# 171-5782_Redux.net
KiCad netlist of a schematic drawn in Altium Designer
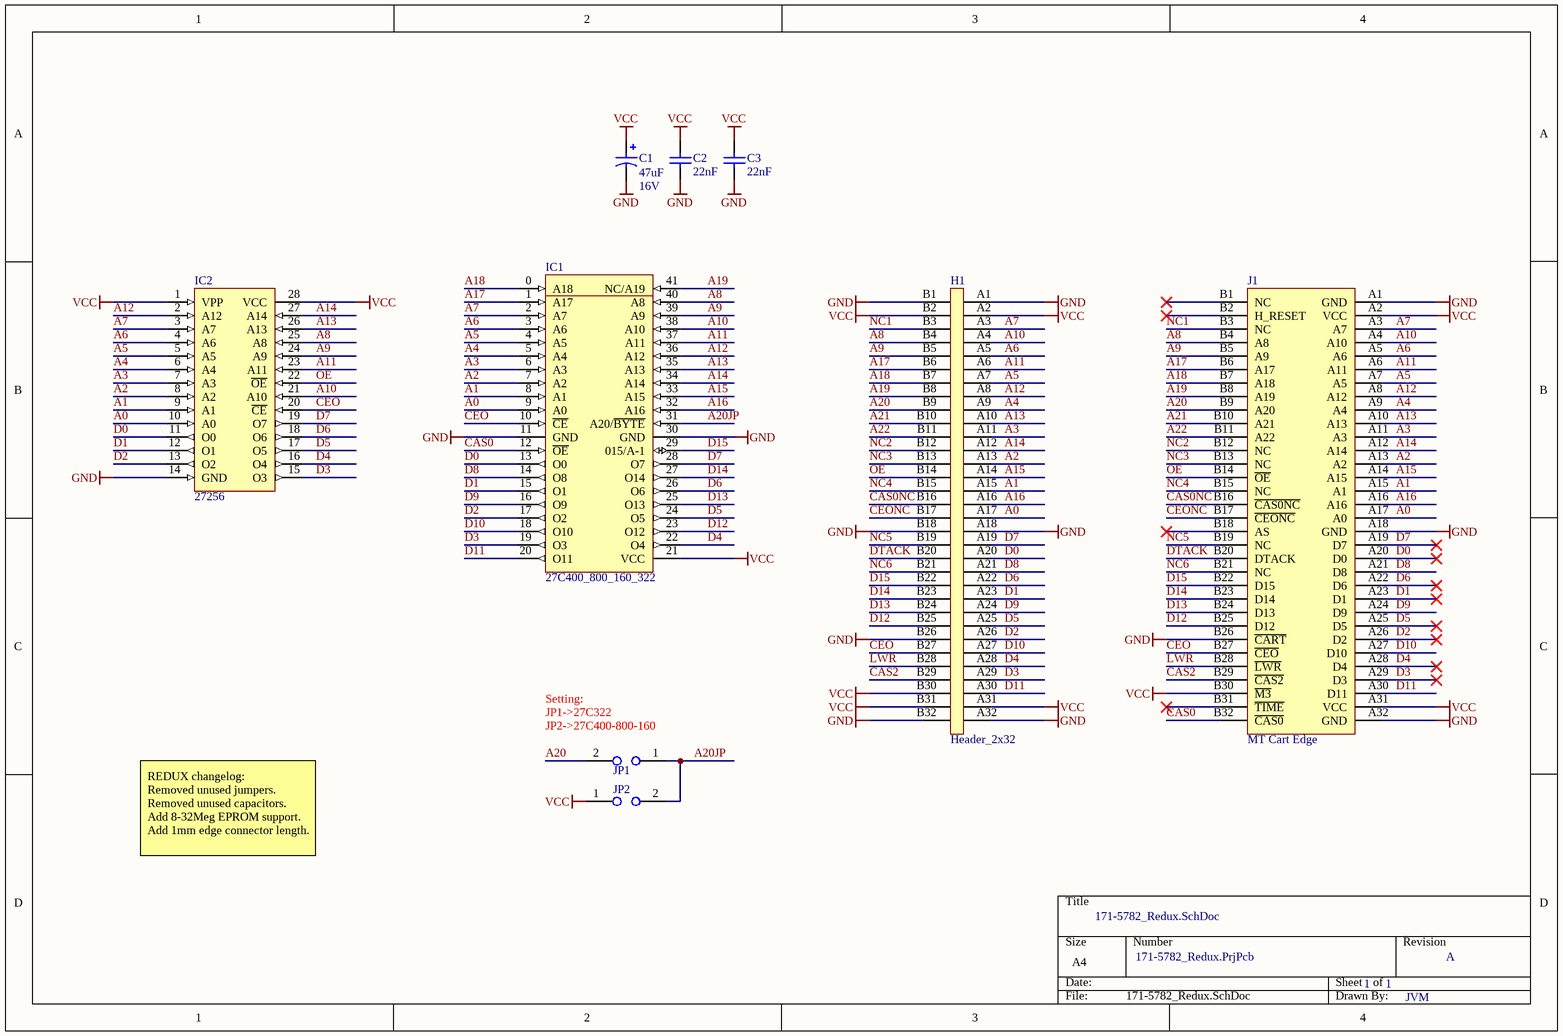
[diagram p0: 171-5782_Redux.SchDoc]

(export (version "E")
  (design (tool "Eeschema 10.0.6"))
  (components
    (comp (ref "C1")
      (value "47uF")
      (footprint "CapPol Mirror")
      (description "Polarized Capacitor, 2.54mm Pitch, 5mm Width, mirrored")
      (fields (field (name "VOLTAGE") "16V") (field (name "Comment") "Cap2.54P5.0D"))
      (libsource (lib "171-5782") (part "Cap2.54P5.0D_mirror"))
    )
    (comp (ref "C2")
      (value "22nF")
      (footprint "CapCer")
      (description "Capacitor (THT), Ceramic, 5.08mm Pitch")
      (fields (field (name "Comment") "CapCer"))
      (libsource (lib "171-5782") (part "CapCer"))
    )
    (comp (ref "C3")
      (value "22nF")
      (footprint "CapCer")
      (description "Capacitor (THT), Ceramic, 5.08mm Pitch")
      (fields (field (name "Comment") "CapCer"))
      (libsource (lib "171-5782") (part "CapCer"))
    )
    (comp (ref "H1")
      (value "Header_2x32")
      (footprint "Header_2x32")
      (libsource (lib "171-5782") (part "Header_2x32"))
    )
    (comp (ref "IC1")
      (value "27C400_800_160_322")
      (footprint "27C400_800_160_322")
      (description "27C400_800_160_322 EPROM combined footprint")
      (libsource (lib "171-5782") (part "27C400_800_160_322"))
    )
    (comp (ref "IC2")
      (value "27256")
      (footprint "27256")
      (description "256K EPROM")
      (libsource (lib "171-5782") (part "27256"))
    )
    (comp (ref "J1")
      (value "MT Cart Edge")
      (footprint "MT_Cart_Edge")
      (libsource (lib "171-5782") (part "MT_CART_EDGE_CON"))
    )
    (comp (ref "JP1")
      (value "SolderBridge")
      (footprint "SOLDER_BRIDGE")
      (description "Solder Bridge")
      (libsource (lib "171-5782") (part "SolderBridge"))
    )
    (comp (ref "JP2")
      (value "SolderBridge")
      (footprint "SOLDER_BRIDGE")
      (description "Solder Bridge")
      (libsource (lib "171-5782") (part "SolderBridge"))
    )
  )
  (nets
    (net (code "1") (name "/A0") (class "Default")
      (node (ref "H1") (pin "A17") (pintype "passive"))
      (node (ref "IC1") (pin "9") (pinfunction "A0_9") (pintype "input"))
      (node (ref "IC2") (pin "10") (pinfunction "A0_10") (pintype "input"))
      (node (ref "J1") (pin "A17") (pinfunction "A0_A17") (pintype "passive"))
    )
    (net (code "2") (name "/A1") (class "Default")
      (node (ref "H1") (pin "A15") (pintype "passive"))
      (node (ref "IC1") (pin "8") (pinfunction "A1_8") (pintype "input"))
      (node (ref "IC2") (pin "9") (pinfunction "A1_9") (pintype "input"))
      (node (ref "J1") (pin "A15") (pinfunction "A1_A15") (pintype "passive"))
    )
    (net (code "3") (name "/A2") (class "Default")
      (node (ref "H1") (pin "A13") (pintype "passive"))
      (node (ref "IC1") (pin "7") (pinfunction "A2_7") (pintype "input"))
      (node (ref "IC2") (pin "8") (pinfunction "A2_8") (pintype "input"))
      (node (ref "J1") (pin "A13") (pinfunction "A2_A13") (pintype "passive"))
    )
    (net (code "4") (name "/A3") (class "Default")
      (node (ref "H1") (pin "A11") (pintype "passive"))
      (node (ref "IC1") (pin "6") (pinfunction "A3_6") (pintype "input"))
      (node (ref "IC2") (pin "7") (pinfunction "A3_7") (pintype "input"))
      (node (ref "J1") (pin "A11") (pinfunction "A3_A11") (pintype "passive"))
    )
    (net (code "5") (name "/A4") (class "Default")
      (node (ref "H1") (pin "A9") (pintype "passive"))
      (node (ref "IC1") (pin "5") (pinfunction "A4_5") (pintype "input"))
      (node (ref "IC2") (pin "6") (pinfunction "A4_6") (pintype "input"))
      (node (ref "J1") (pin "A9") (pinfunction "A4_A9") (pintype "passive"))
    )
    (net (code "6") (name "/A5") (class "Default")
      (node (ref "H1") (pin "A7") (pintype "passive"))
      (node (ref "IC1") (pin "4") (pinfunction "A5_4") (pintype "input"))
      (node (ref "IC2") (pin "5") (pinfunction "A5_5") (pintype "input"))
      (node (ref "J1") (pin "A7") (pinfunction "A5_A7") (pintype "passive"))
    )
    (net (code "7") (name "/A6") (class "Default")
      (node (ref "H1") (pin "A5") (pintype "passive"))
      (node (ref "IC1") (pin "3") (pinfunction "A6_3") (pintype "input"))
      (node (ref "IC2") (pin "4") (pinfunction "A6_4") (pintype "input"))
      (node (ref "J1") (pin "A5") (pinfunction "A6_A5") (pintype "passive"))
    )
    (net (code "8") (name "/A7") (class "Default")
      (node (ref "H1") (pin "A3") (pintype "passive"))
      (node (ref "IC1") (pin "2") (pinfunction "A7_2") (pintype "input"))
      (node (ref "IC2") (pin "3") (pinfunction "A7_3") (pintype "input"))
      (node (ref "J1") (pin "A3") (pinfunction "A7_A3") (pintype "passive"))
    )
    (net (code "9") (name "/A8") (class "Default")
      (node (ref "H1") (pin "B4") (pintype "passive"))
      (node (ref "IC1") (pin "40") (pinfunction "A8_40") (pintype "input"))
      (node (ref "IC2") (pin "25") (pinfunction "A8_25") (pintype "input"))
      (node (ref "J1") (pin "B4") (pinfunction "A8_B4") (pintype "passive"))
    )
    (net (code "10") (name "/A9") (class "Default")
      (node (ref "H1") (pin "B5") (pintype "passive"))
      (node (ref "IC1") (pin "39") (pinfunction "A9_39") (pintype "input"))
      (node (ref "IC2") (pin "24") (pinfunction "A9_24") (pintype "input"))
      (node (ref "J1") (pin "B5") (pinfunction "A9_B5") (pintype "passive"))
    )
    (net (code "11") (name "/A10") (class "Default")
      (node (ref "H1") (pin "A4") (pintype "passive"))
      (node (ref "IC1") (pin "38") (pinfunction "A10_38") (pintype "input"))
      (node (ref "IC2") (pin "21") (pinfunction "A10_21") (pintype "input"))
      (node (ref "J1") (pin "A4") (pinfunction "A10_A4") (pintype "passive"))
    )
    (net (code "12") (name "/A11") (class "Default")
      (node (ref "H1") (pin "A6") (pintype "passive"))
      (node (ref "IC1") (pin "37") (pinfunction "A11_37") (pintype "input"))
      (node (ref "IC2") (pin "23") (pinfunction "A11_23") (pintype "input"))
      (node (ref "J1") (pin "A6") (pinfunction "A11_A6") (pintype "passive"))
    )
    (net (code "13") (name "/A12") (class "Default")
      (node (ref "H1") (pin "A8") (pintype "passive"))
      (node (ref "IC1") (pin "36") (pinfunction "A12_36") (pintype "input"))
      (node (ref "IC2") (pin "2") (pinfunction "A12_2") (pintype "input"))
      (node (ref "J1") (pin "A8") (pinfunction "A12_A8") (pintype "passive"))
    )
    (net (code "14") (name "/A13") (class "Default")
      (node (ref "H1") (pin "A10") (pintype "passive"))
      (node (ref "IC1") (pin "35") (pinfunction "A13_35") (pintype "input"))
      (node (ref "IC2") (pin "26") (pinfunction "A13_26") (pintype "input"))
      (node (ref "J1") (pin "A10") (pinfunction "A13_A10") (pintype "passive"))
    )
    (net (code "15") (name "/A14") (class "Default")
      (node (ref "H1") (pin "A12") (pintype "passive"))
      (node (ref "IC1") (pin "34") (pinfunction "A14_34") (pintype "input"))
      (node (ref "IC2") (pin "27") (pinfunction "A14_27") (pintype "input"))
      (node (ref "J1") (pin "A12") (pinfunction "A14_A12") (pintype "passive"))
    )
    (net (code "16") (name "/A15") (class "Default")
      (node (ref "H1") (pin "A14") (pintype "passive"))
      (node (ref "IC1") (pin "33") (pinfunction "A15_33") (pintype "input"))
      (node (ref "J1") (pin "A14") (pinfunction "A15_A14") (pintype "passive"))
    )
    (net (code "17") (name "/A16") (class "Default")
      (node (ref "H1") (pin "A16") (pintype "passive"))
      (node (ref "IC1") (pin "32") (pinfunction "A16_32") (pintype "input"))
      (node (ref "J1") (pin "A16") (pinfunction "A16_A16") (pintype "passive"))
    )
    (net (code "18") (name "/A17") (class "Default")
      (node (ref "H1") (pin "B6") (pintype "passive"))
      (node (ref "IC1") (pin "1") (pinfunction "A17_1") (pintype "input"))
      (node (ref "J1") (pin "B6") (pinfunction "A17_B6") (pintype "passive"))
    )
    (net (code "19") (name "/A18") (class "Default")
      (node (ref "H1") (pin "B7") (pintype "passive"))
      (node (ref "IC1") (pin "0") (pinfunction "A18_0") (pintype "input"))
      (node (ref "J1") (pin "B7") (pinfunction "A18_B7") (pintype "passive"))
    )
    (net (code "20") (name "/A19") (class "Default")
      (node (ref "H1") (pin "B8") (pintype "passive"))
      (node (ref "IC1") (pin "41") (pinfunction "NC/A19_41") (pintype "input"))
      (node (ref "J1") (pin "B8") (pinfunction "A19_B8") (pintype "passive"))
    )
    (net (code "21") (name "/A20") (class "Default")
      (node (ref "H1") (pin "B9") (pintype "passive"))
      (node (ref "J1") (pin "B9") (pinfunction "A20_B9") (pintype "passive"))
      (node (ref "JP1") (pin "2") (pinfunction "2_2") (pintype "passive"))
    )
    (net (code "22") (name "/A20JP") (class "Default")
      (node (ref "IC1") (pin "31") (pinfunction "A20/~{BYTE}_31") (pintype "input"))
      (node (ref "JP1") (pin "1") (pinfunction "1_1") (pintype "passive"))
      (node (ref "JP2") (pin "2") (pinfunction "2_2") (pintype "passive"))
    )
    (net (code "23") (name "/A21") (class "Default")
      (node (ref "H1") (pin "B10") (pintype "passive"))
      (node (ref "J1") (pin "B10") (pinfunction "A21_B10") (pintype "passive"))
    )
    (net (code "24") (name "/A22") (class "Default")
      (node (ref "H1") (pin "B11") (pintype "passive"))
      (node (ref "J1") (pin "B11") (pinfunction "A22_B11") (pintype "passive"))
    )
    (net (code "25") (name "/CAS0") (class "Default")
      (node (ref "IC1") (pin "12") (pinfunction "~{OE}_12") (pintype "input"))
      (node (ref "J1") (pin "B32") (pinfunction "~{CAS0}_B32") (pintype "passive"))
    )
    (net (code "26") (name "/CAS0NC") (class "Default")
      (node (ref "H1") (pin "B16") (pintype "passive"))
      (node (ref "J1") (pin "B16") (pinfunction "~{CAS0NC}_B16") (pintype "passive"))
    )
    (net (code "27") (name "/CAS2") (class "Default")
      (node (ref "H1") (pin "B29") (pintype "passive"))
      (node (ref "J1") (pin "B29") (pinfunction "~{CAS2}_B29") (pintype "passive"))
    )
    (net (code "28") (name "/CEO") (class "Default")
      (node (ref "H1") (pin "B27") (pintype "passive"))
      (node (ref "IC1") (pin "10") (pinfunction "~{CE}_10") (pintype "input"))
      (node (ref "IC2") (pin "20") (pinfunction "~{CE}_20") (pintype "input"))
      (node (ref "J1") (pin "B27") (pinfunction "~{CEO}_B27") (pintype "passive"))
    )
    (net (code "29") (name "/CEONC") (class "Default")
      (node (ref "H1") (pin "B17") (pintype "passive"))
      (node (ref "J1") (pin "B17") (pinfunction "~{CEONC}_B17") (pintype "passive"))
    )
    (net (code "30") (name "/D0") (class "Default")
      (node (ref "H1") (pin "A20") (pintype "passive"))
      (node (ref "IC1") (pin "13") (pinfunction "O0_13") (pintype "output"))
      (node (ref "IC2") (pin "11") (pinfunction "O0_11") (pintype "output"))
      (node (ref "J1") (pin "A20") (pinfunction "D0_A20") (pintype "passive"))
    )
    (net (code "31") (name "/D1") (class "Default")
      (node (ref "H1") (pin "A23") (pintype "passive"))
      (node (ref "IC1") (pin "15") (pinfunction "O1_15") (pintype "output"))
      (node (ref "IC2") (pin "12") (pinfunction "O1_12") (pintype "output"))
      (node (ref "J1") (pin "A23") (pinfunction "D1_A23") (pintype "passive"))
    )
    (net (code "32") (name "/D2") (class "Default")
      (node (ref "H1") (pin "A26") (pintype "passive"))
      (node (ref "IC1") (pin "17") (pinfunction "O2_17") (pintype "output"))
      (node (ref "IC2") (pin "13") (pinfunction "O2_13") (pintype "output"))
      (node (ref "J1") (pin "A26") (pinfunction "D2_A26") (pintype "passive"))
    )
    (net (code "33") (name "/D3") (class "Default")
      (node (ref "H1") (pin "A29") (pintype "passive"))
      (node (ref "IC1") (pin "19") (pinfunction "O3_19") (pintype "output"))
      (node (ref "IC2") (pin "15") (pinfunction "O3_15") (pintype "output"))
      (node (ref "J1") (pin "A29") (pinfunction "D3_A29") (pintype "passive"))
    )
    (net (code "34") (name "/D4") (class "Default")
      (node (ref "H1") (pin "A28") (pintype "passive"))
      (node (ref "IC1") (pin "22") (pinfunction "O4_22") (pintype "output"))
      (node (ref "IC2") (pin "16") (pinfunction "O4_16") (pintype "output"))
      (node (ref "J1") (pin "A28") (pinfunction "D4_A28") (pintype "passive"))
    )
    (net (code "35") (name "/D5") (class "Default")
      (node (ref "H1") (pin "A25") (pintype "passive"))
      (node (ref "IC1") (pin "24") (pinfunction "O5_24") (pintype "output"))
      (node (ref "IC2") (pin "17") (pinfunction "O5_17") (pintype "output"))
      (node (ref "J1") (pin "A25") (pinfunction "D5_A25") (pintype "passive"))
    )
    (net (code "36") (name "/D6") (class "Default")
      (node (ref "H1") (pin "A22") (pintype "passive"))
      (node (ref "IC1") (pin "26") (pinfunction "O6_26") (pintype "output"))
      (node (ref "IC2") (pin "18") (pinfunction "O6_18") (pintype "output"))
      (node (ref "J1") (pin "A22") (pinfunction "D6_A22") (pintype "passive"))
    )
    (net (code "37") (name "/D7") (class "Default")
      (node (ref "H1") (pin "A19") (pintype "passive"))
      (node (ref "IC1") (pin "28") (pinfunction "O7_28") (pintype "output"))
      (node (ref "IC2") (pin "19") (pinfunction "O7_19") (pintype "output"))
      (node (ref "J1") (pin "A19") (pinfunction "D7_A19") (pintype "passive"))
    )
    (net (code "38") (name "/D8") (class "Default")
      (node (ref "H1") (pin "A21") (pintype "passive"))
      (node (ref "IC1") (pin "14") (pinfunction "O8_14") (pintype "output"))
      (node (ref "J1") (pin "A21") (pinfunction "D8_A21") (pintype "passive"))
    )
    (net (code "39") (name "/D9") (class "Default")
      (node (ref "H1") (pin "A24") (pintype "passive"))
      (node (ref "IC1") (pin "16") (pinfunction "O9_16") (pintype "output"))
      (node (ref "J1") (pin "A24") (pinfunction "D9_A24") (pintype "passive"))
    )
    (net (code "40") (name "/D10") (class "Default")
      (node (ref "H1") (pin "A27") (pintype "passive"))
      (node (ref "IC1") (pin "18") (pinfunction "O10_18") (pintype "output"))
      (node (ref "J1") (pin "A27") (pinfunction "D10_A27") (pintype "passive"))
    )
    (net (code "41") (name "/D11") (class "Default")
      (node (ref "H1") (pin "A30") (pintype "passive"))
      (node (ref "IC1") (pin "20") (pinfunction "O11_20") (pintype "output"))
      (node (ref "J1") (pin "A30") (pinfunction "D11_A30") (pintype "passive"))
    )
    (net (code "42") (name "/D12") (class "Default")
      (node (ref "H1") (pin "B25") (pintype "passive"))
      (node (ref "IC1") (pin "23") (pinfunction "O12_23") (pintype "output"))
      (node (ref "J1") (pin "B25") (pinfunction "D12_B25") (pintype "passive"))
    )
    (net (code "43") (name "/D13") (class "Default")
      (node (ref "H1") (pin "B24") (pintype "passive"))
      (node (ref "IC1") (pin "25") (pinfunction "O13_25") (pintype "output"))
      (node (ref "J1") (pin "B24") (pinfunction "D13_B24") (pintype "passive"))
    )
    (net (code "44") (name "/D14") (class "Default")
      (node (ref "H1") (pin "B23") (pintype "passive"))
      (node (ref "IC1") (pin "27") (pinfunction "O14_27") (pintype "output"))
      (node (ref "J1") (pin "B23") (pinfunction "D14_B23") (pintype "passive"))
    )
    (net (code "45") (name "/D15") (class "Default")
      (node (ref "H1") (pin "B22") (pintype "passive"))
      (node (ref "IC1") (pin "29") (pinfunction "015/A-1_29") (pintype "bidirectional"))
      (node (ref "J1") (pin "B22") (pinfunction "D15_B22") (pintype "passive"))
    )
    (net (code "46") (name "/DTACK") (class "Default")
      (node (ref "H1") (pin "B20") (pintype "passive"))
      (node (ref "J1") (pin "B20") (pinfunction "DTACK_B20") (pintype "passive"))
    )
    (net (code "47") (name "/LWR") (class "Default")
      (node (ref "H1") (pin "B28") (pintype "passive"))
      (node (ref "J1") (pin "B28") (pinfunction "~{LWR}_B28") (pintype "passive"))
    )
    (net (code "48") (name "/NC1") (class "Default")
      (node (ref "H1") (pin "B3") (pintype "passive"))
      (node (ref "J1") (pin "B3") (pinfunction "NC_B3") (pintype "passive"))
    )
    (net (code "49") (name "/NC2") (class "Default")
      (node (ref "H1") (pin "B12") (pintype "passive"))
      (node (ref "J1") (pin "B12") (pinfunction "NC_B12") (pintype "passive"))
    )
    (net (code "50") (name "/NC3") (class "Default")
      (node (ref "H1") (pin "B13") (pintype "passive"))
      (node (ref "J1") (pin "B13") (pinfunction "NC_B13") (pintype "passive"))
    )
    (net (code "51") (name "/NC4") (class "Default")
      (node (ref "H1") (pin "B15") (pintype "passive"))
      (node (ref "J1") (pin "B15") (pinfunction "NC_B15") (pintype "passive"))
    )
    (net (code "52") (name "/NC5") (class "Default")
      (node (ref "H1") (pin "B19") (pintype "passive"))
      (node (ref "J1") (pin "B19") (pinfunction "NC_B19") (pintype "passive"))
    )
    (net (code "53") (name "/NC6") (class "Default")
      (node (ref "H1") (pin "B21") (pintype "passive"))
      (node (ref "J1") (pin "B21") (pinfunction "NC_B21") (pintype "passive"))
    )
    (net (code "54") (name "/OE") (class "Default")
      (node (ref "H1") (pin "B14") (pintype "passive"))
      (node (ref "IC2") (pin "22") (pinfunction "~{OE}_22") (pintype "input"))
      (node (ref "J1") (pin "B14") (pinfunction "~{OE}_B14") (pintype "passive"))
    )
    (net (code "55") (name "GND") (class "Default")
      (node (ref "C1") (pin "2") (pinfunction "2_2") (pintype "passive"))
      (node (ref "C2") (pin "1") (pinfunction "1_1") (pintype "passive"))
      (node (ref "C3") (pin "1") (pinfunction "1_1") (pintype "passive"))
      (node (ref "H1") (pin "A1") (pintype "passive"))
      (node (ref "H1") (pin "A18") (pintype "passive"))
      (node (ref "H1") (pin "A32") (pintype "passive"))
      (node (ref "H1") (pin "B1") (pintype "passive"))
      (node (ref "H1") (pin "B18") (pintype "passive"))
      (node (ref "H1") (pin "B26") (pintype "passive"))
      (node (ref "H1") (pin "B32") (pintype "passive"))
      (node (ref "IC1") (pin "11") (pinfunction "GND_11") (pintype "power_in"))
      (node (ref "IC1") (pin "30") (pinfunction "GND_30") (pintype "power_in"))
      (node (ref "IC2") (pin "14") (pinfunction "GND_14") (pintype "input"))
      (node (ref "J1") (pin "A1") (pinfunction "GND_A1") (pintype "passive"))
      (node (ref "J1") (pin "A18") (pinfunction "GND_A18") (pintype "passive"))
      (node (ref "J1") (pin "A32") (pinfunction "GND_A32") (pintype "passive"))
      (node (ref "J1") (pin "B26") (pinfunction "~{CART}_B26") (pintype "passive"))
    )
    (net (code "56") (name "VCC") (class "Default")
      (node (ref "C1") (pin "1") (pinfunction "1_1") (pintype "passive"))
      (node (ref "C2") (pin "2") (pinfunction "2_2") (pintype "passive"))
      (node (ref "C3") (pin "2") (pinfunction "2_2") (pintype "passive"))
      (node (ref "H1") (pin "A2") (pintype "passive"))
      (node (ref "H1") (pin "A31") (pintype "passive"))
      (node (ref "H1") (pin "B2") (pintype "passive"))
      (node (ref "H1") (pin "B30") (pintype "passive"))
      (node (ref "H1") (pin "B31") (pintype "passive"))
      (node (ref "IC1") (pin "21") (pinfunction "VCC_21") (pintype "power_in"))
      (node (ref "IC2") (pin "1") (pinfunction "VPP_1") (pintype "input"))
      (node (ref "IC2") (pin "28") (pinfunction "VCC_28") (pintype "power_in"))
      (node (ref "J1") (pin "A2") (pinfunction "VCC_A2") (pintype "passive"))
      (node (ref "J1") (pin "A31") (pinfunction "VCC_A31") (pintype "passive"))
      (node (ref "J1") (pin "B30") (pinfunction "~{M3}_B30") (pintype "passive"))
      (node (ref "JP2") (pin "1") (pinfunction "1_1") (pintype "passive"))
    )
    (net (code "57") (name "unconnected-(J1-AS-PadB18)") (class "Default")
      (node (ref "J1") (pin "B18") (pinfunction "AS_B18") (pintype "passive+no_connect"))
    )
    (net (code "58") (name "unconnected-(J1-H_RESET-PadB2)") (class "Default")
      (node (ref "J1") (pin "B2") (pinfunction "H_RESET_B2") (pintype "passive+no_connect"))
    )
    (net (code "59") (name "unconnected-(J1-NC-PadB1)") (class "Default")
      (node (ref "J1") (pin "B1") (pinfunction "NC_B1") (pintype "passive+no_connect"))
    )
    (net (code "60") (name "unconnected-(J1-~{TIME}-PadB31)") (class "Default")
      (node (ref "J1") (pin "B31") (pinfunction "~{TIME}_B31") (pintype "passive+no_connect"))
    )
  )
)
